# axiom_beta_plugin_module_3xPMOD_v1_1.net
KiCad netlist of a schematic drawn in EAGLE
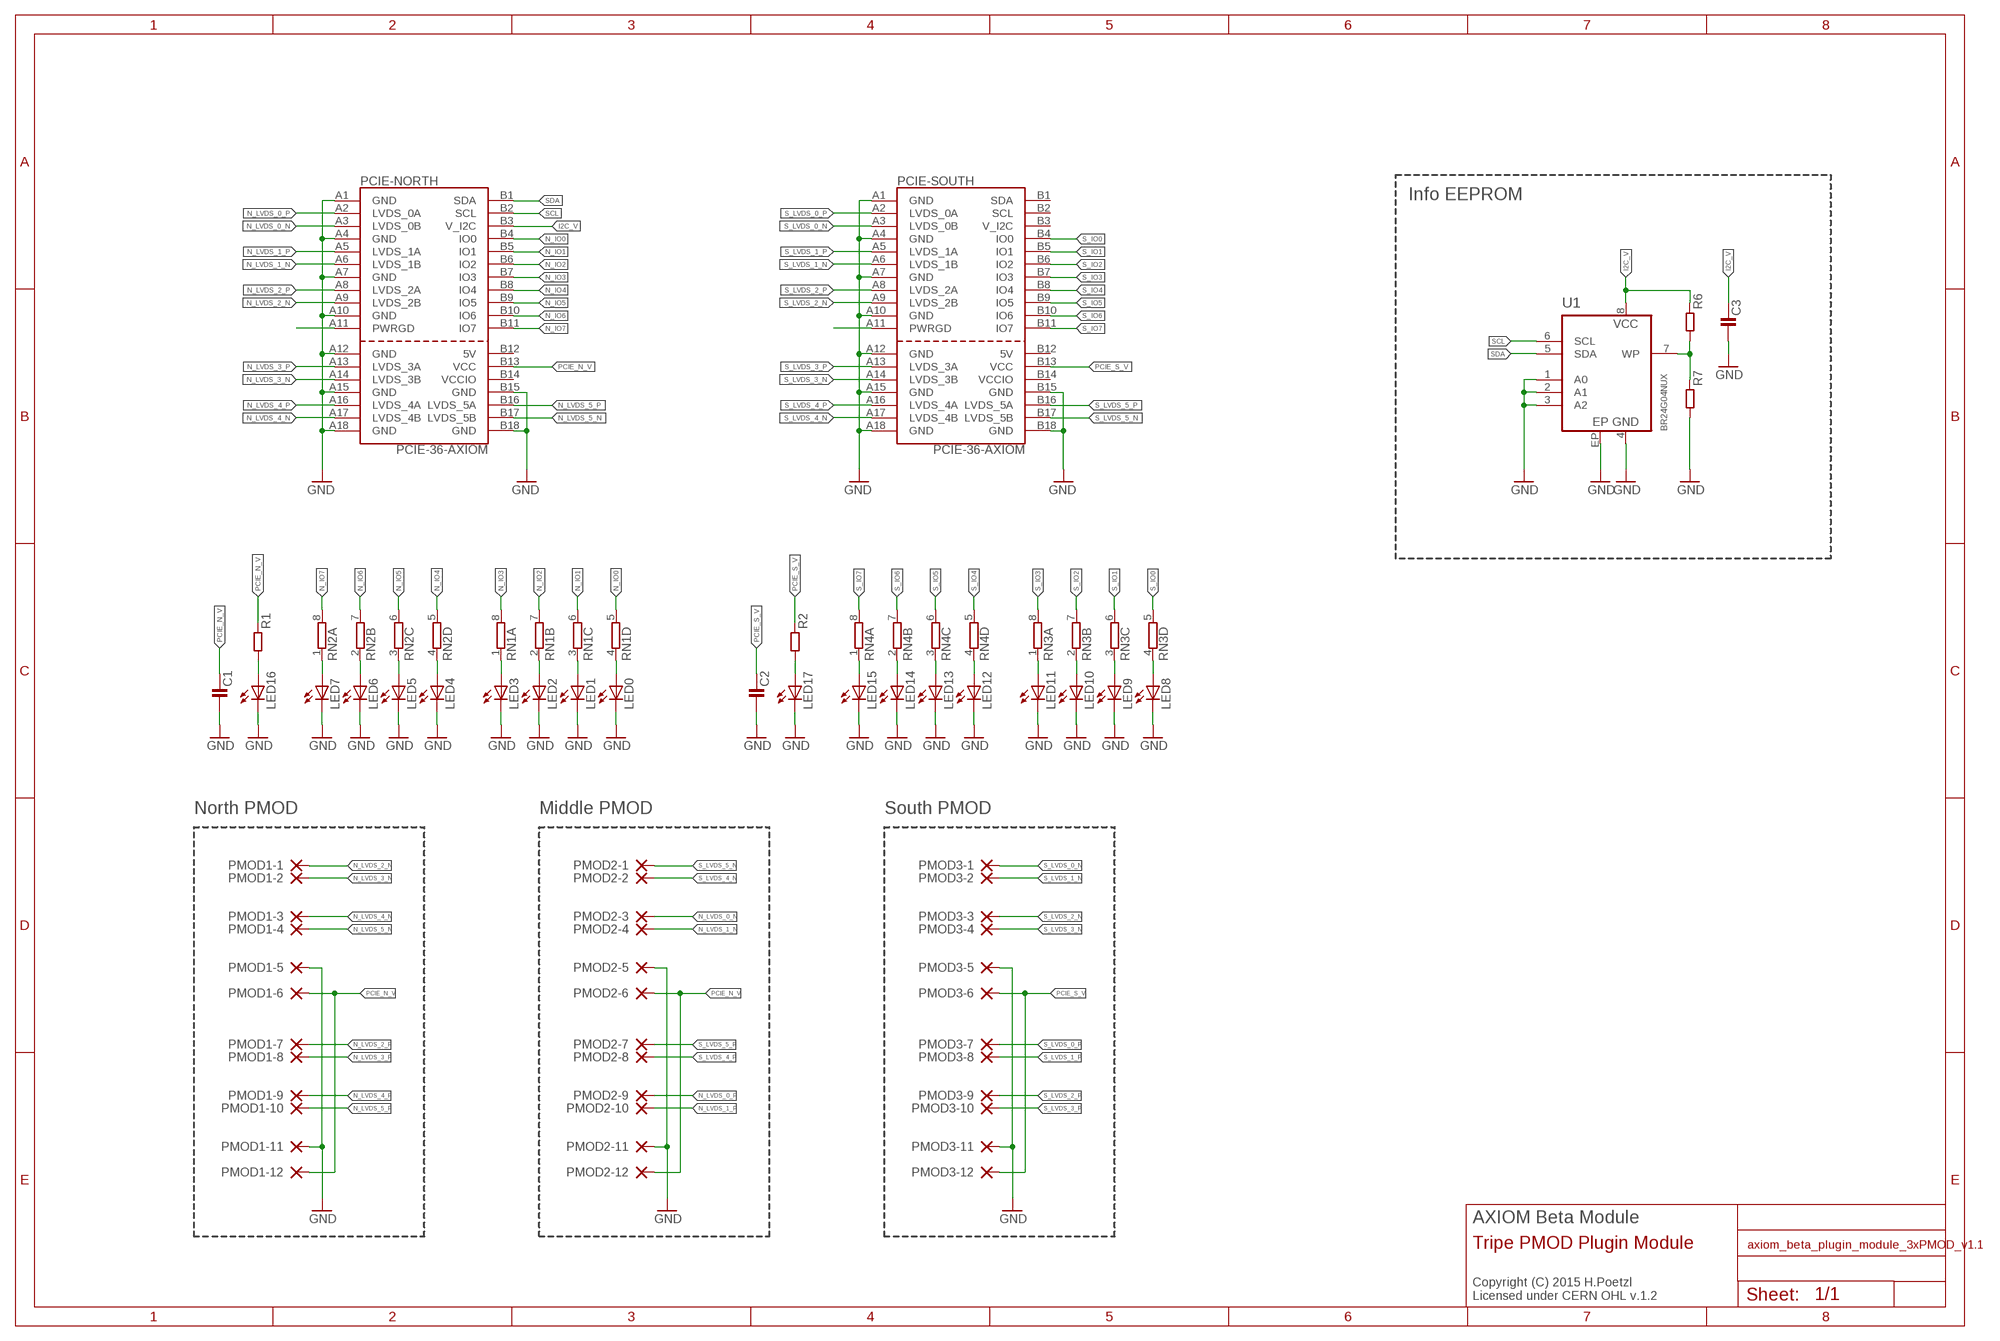
[diagram p0: schematic, sheet 1]

(export (version "E")
  (design (tool "Eeschema 10.0.6"))
  (components
    (comp (ref "C1")
      (value "C1206-A")
      (footprint "eagle-import:1206-A")
      (libsource (lib "eagle-import") (part "C1206-A"))
    )
    (comp (ref "C2")
      (value "C1206-A")
      (footprint "eagle-import:1206-A")
      (libsource (lib "eagle-import") (part "C1206-A"))
    )
    (comp (ref "C3")
      (value "C0402-B")
      (footprint "eagle-import:0402-B")
      (libsource (lib "eagle-import") (part "C0402-B"))
    )
    (comp (ref "LED0")
      (value "LEDCHIPLED_0603")
      (footprint "eagle-import:CHIPLED_0603")
      (libsource (lib "eagle-import") (part "LEDCHIPLED_0603"))
    )
    (comp (ref "LED1")
      (value "LEDCHIPLED_0603")
      (footprint "eagle-import:CHIPLED_0603")
      (libsource (lib "eagle-import") (part "LEDCHIPLED_0603"))
    )
    (comp (ref "LED2")
      (value "LEDCHIPLED_0603")
      (footprint "eagle-import:CHIPLED_0603")
      (libsource (lib "eagle-import") (part "LEDCHIPLED_0603"))
    )
    (comp (ref "LED3")
      (value "LEDCHIPLED_0603")
      (footprint "eagle-import:CHIPLED_0603")
      (libsource (lib "eagle-import") (part "LEDCHIPLED_0603"))
    )
    (comp (ref "LED4")
      (value "LEDCHIPLED_0603")
      (footprint "eagle-import:CHIPLED_0603")
      (libsource (lib "eagle-import") (part "LEDCHIPLED_0603"))
    )
    (comp (ref "LED5")
      (value "LEDCHIPLED_0603")
      (footprint "eagle-import:CHIPLED_0603")
      (libsource (lib "eagle-import") (part "LEDCHIPLED_0603"))
    )
    (comp (ref "LED6")
      (value "LEDCHIPLED_0603")
      (footprint "eagle-import:CHIPLED_0603")
      (libsource (lib "eagle-import") (part "LEDCHIPLED_0603"))
    )
    (comp (ref "LED7")
      (value "LEDCHIPLED_0603")
      (footprint "eagle-import:CHIPLED_0603")
      (libsource (lib "eagle-import") (part "LEDCHIPLED_0603"))
    )
    (comp (ref "LED8")
      (value "LEDCHIPLED_0603")
      (footprint "eagle-import:CHIPLED_0603")
      (libsource (lib "eagle-import") (part "LEDCHIPLED_0603"))
    )
    (comp (ref "LED9")
      (value "LEDCHIPLED_0603")
      (footprint "eagle-import:CHIPLED_0603")
      (libsource (lib "eagle-import") (part "LEDCHIPLED_0603"))
    )
    (comp (ref "LED10")
      (value "LEDCHIPLED_0603")
      (footprint "eagle-import:CHIPLED_0603")
      (libsource (lib "eagle-import") (part "LEDCHIPLED_0603"))
    )
    (comp (ref "LED11")
      (value "LEDCHIPLED_0603")
      (footprint "eagle-import:CHIPLED_0603")
      (libsource (lib "eagle-import") (part "LEDCHIPLED_0603"))
    )
    (comp (ref "LED12")
      (value "LEDCHIPLED_0603")
      (footprint "eagle-import:CHIPLED_0603")
      (libsource (lib "eagle-import") (part "LEDCHIPLED_0603"))
    )
    (comp (ref "LED13")
      (value "LEDCHIPLED_0603")
      (footprint "eagle-import:CHIPLED_0603")
      (libsource (lib "eagle-import") (part "LEDCHIPLED_0603"))
    )
    (comp (ref "LED14")
      (value "LEDCHIPLED_0603")
      (footprint "eagle-import:CHIPLED_0603")
      (libsource (lib "eagle-import") (part "LEDCHIPLED_0603"))
    )
    (comp (ref "LED15")
      (value "LEDCHIPLED_0603")
      (footprint "eagle-import:CHIPLED_0603")
      (libsource (lib "eagle-import") (part "LEDCHIPLED_0603"))
    )
    (comp (ref "LED16")
      (value "LEDCHIPLED_0603")
      (footprint "eagle-import:CHIPLED_0603")
      (libsource (lib "eagle-import") (part "LEDCHIPLED_0603"))
    )
    (comp (ref "LED17")
      (value "LEDCHIPLED_0603")
      (footprint "eagle-import:CHIPLED_0603")
      (libsource (lib "eagle-import") (part "LEDCHIPLED_0603"))
    )
    (comp (ref "PCIE-NORTH")
      (value "PCIE-36-AXIOM")
      (footprint "eagle-import:PCIE-36-AXIOM")
      (libsource (lib "eagle-import") (part "PCIE-36-AXIOM"))
    )
    (comp (ref "PCIE-SOUTH")
      (value "PCIE-36-AXIOM")
      (footprint "eagle-import:PCIE-36-AXIOM")
      (libsource (lib "eagle-import") (part "PCIE-36-AXIOM"))
    )
    (comp (ref "PMOD1-1")
      (value "SMD-PAD1.6X3.8MM-U")
      (footprint "eagle-import:1.6X3.8U-MM")
      (libsource (lib "eagle-import") (part "SMD-PAD1.6X3.8MM-U"))
    )
    (comp (ref "PMOD1-2")
      (value "SMD-PAD1.6X3.8MM-U")
      (footprint "eagle-import:1.6X3.8U-MM")
      (libsource (lib "eagle-import") (part "SMD-PAD1.6X3.8MM-U"))
    )
    (comp (ref "PMOD1-3")
      (value "SMD-PAD1.6X3.8MM-U")
      (footprint "eagle-import:1.6X3.8U-MM")
      (libsource (lib "eagle-import") (part "SMD-PAD1.6X3.8MM-U"))
    )
    (comp (ref "PMOD1-4")
      (value "SMD-PAD1.6X3.8MM-U")
      (footprint "eagle-import:1.6X3.8U-MM")
      (libsource (lib "eagle-import") (part "SMD-PAD1.6X3.8MM-U"))
    )
    (comp (ref "PMOD1-5")
      (value "SMD-PAD1.6X3.8MM-U")
      (footprint "eagle-import:1.6X3.8U-MM")
      (libsource (lib "eagle-import") (part "SMD-PAD1.6X3.8MM-U"))
    )
    (comp (ref "PMOD1-6")
      (value "SMD-PAD1.6X3.8MM-U")
      (footprint "eagle-import:1.6X3.8U-MM")
      (libsource (lib "eagle-import") (part "SMD-PAD1.6X3.8MM-U"))
    )
    (comp (ref "PMOD1-7")
      (value "SMD-PAD1.6X3.8MM-U")
      (footprint "eagle-import:1.6X3.8U-MM")
      (libsource (lib "eagle-import") (part "SMD-PAD1.6X3.8MM-U"))
    )
    (comp (ref "PMOD1-8")
      (value "SMD-PAD1.6X3.8MM-U")
      (footprint "eagle-import:1.6X3.8U-MM")
      (libsource (lib "eagle-import") (part "SMD-PAD1.6X3.8MM-U"))
    )
    (comp (ref "PMOD1-9")
      (value "SMD-PAD1.6X3.8MM-U")
      (footprint "eagle-import:1.6X3.8U-MM")
      (libsource (lib "eagle-import") (part "SMD-PAD1.6X3.8MM-U"))
    )
    (comp (ref "PMOD1-10")
      (value "SMD-PAD1.6X3.8MM-U")
      (footprint "eagle-import:1.6X3.8U-MM")
      (libsource (lib "eagle-import") (part "SMD-PAD1.6X3.8MM-U"))
    )
    (comp (ref "PMOD1-11")
      (value "SMD-PAD1.6X3.8MM-U")
      (footprint "eagle-import:1.6X3.8U-MM")
      (libsource (lib "eagle-import") (part "SMD-PAD1.6X3.8MM-U"))
    )
    (comp (ref "PMOD1-12")
      (value "SMD-PAD1.6X3.8MM-U")
      (footprint "eagle-import:1.6X3.8U-MM")
      (libsource (lib "eagle-import") (part "SMD-PAD1.6X3.8MM-U"))
    )
    (comp (ref "PMOD2-1")
      (value "SMD-PAD1.6X3.8MM-U")
      (footprint "eagle-import:1.6X3.8U-MM")
      (libsource (lib "eagle-import") (part "SMD-PAD1.6X3.8MM-U"))
    )
    (comp (ref "PMOD2-2")
      (value "SMD-PAD1.6X3.8MM-U")
      (footprint "eagle-import:1.6X3.8U-MM")
      (libsource (lib "eagle-import") (part "SMD-PAD1.6X3.8MM-U"))
    )
    (comp (ref "PMOD2-3")
      (value "SMD-PAD1.6X3.8MM-U")
      (footprint "eagle-import:1.6X3.8U-MM")
      (libsource (lib "eagle-import") (part "SMD-PAD1.6X3.8MM-U"))
    )
    (comp (ref "PMOD2-4")
      (value "SMD-PAD1.6X3.8MM-U")
      (footprint "eagle-import:1.6X3.8U-MM")
      (libsource (lib "eagle-import") (part "SMD-PAD1.6X3.8MM-U"))
    )
    (comp (ref "PMOD2-5")
      (value "SMD-PAD1.6X3.8MM-U")
      (footprint "eagle-import:1.6X3.8U-MM")
      (libsource (lib "eagle-import") (part "SMD-PAD1.6X3.8MM-U"))
    )
    (comp (ref "PMOD2-6")
      (value "SMD-PAD1.6X3.8MM-U")
      (footprint "eagle-import:1.6X3.8U-MM")
      (libsource (lib "eagle-import") (part "SMD-PAD1.6X3.8MM-U"))
    )
    (comp (ref "PMOD2-7")
      (value "SMD-PAD1.6X3.8MM-U")
      (footprint "eagle-import:1.6X3.8U-MM")
      (libsource (lib "eagle-import") (part "SMD-PAD1.6X3.8MM-U"))
    )
    (comp (ref "PMOD2-8")
      (value "SMD-PAD1.6X3.8MM-U")
      (footprint "eagle-import:1.6X3.8U-MM")
      (libsource (lib "eagle-import") (part "SMD-PAD1.6X3.8MM-U"))
    )
    (comp (ref "PMOD2-9")
      (value "SMD-PAD1.6X3.8MM-U")
      (footprint "eagle-import:1.6X3.8U-MM")
      (libsource (lib "eagle-import") (part "SMD-PAD1.6X3.8MM-U"))
    )
    (comp (ref "PMOD2-10")
      (value "SMD-PAD1.6X3.8MM-U")
      (footprint "eagle-import:1.6X3.8U-MM")
      (libsource (lib "eagle-import") (part "SMD-PAD1.6X3.8MM-U"))
    )
    (comp (ref "PMOD2-11")
      (value "SMD-PAD1.6X3.8MM-U")
      (footprint "eagle-import:1.6X3.8U-MM")
      (libsource (lib "eagle-import") (part "SMD-PAD1.6X3.8MM-U"))
    )
    (comp (ref "PMOD2-12")
      (value "SMD-PAD1.6X3.8MM-U")
      (footprint "eagle-import:1.6X3.8U-MM")
      (libsource (lib "eagle-import") (part "SMD-PAD1.6X3.8MM-U"))
    )
    (comp (ref "PMOD3-1")
      (value "SMD-PAD1.6X3.8MM-U")
      (footprint "eagle-import:1.6X3.8U-MM")
      (libsource (lib "eagle-import") (part "SMD-PAD1.6X3.8MM-U"))
    )
    (comp (ref "PMOD3-2")
      (value "SMD-PAD1.6X3.8MM-U")
      (footprint "eagle-import:1.6X3.8U-MM")
      (libsource (lib "eagle-import") (part "SMD-PAD1.6X3.8MM-U"))
    )
    (comp (ref "PMOD3-3")
      (value "SMD-PAD1.6X3.8MM-U")
      (footprint "eagle-import:1.6X3.8U-MM")
      (libsource (lib "eagle-import") (part "SMD-PAD1.6X3.8MM-U"))
    )
    (comp (ref "PMOD3-4")
      (value "SMD-PAD1.6X3.8MM-U")
      (footprint "eagle-import:1.6X3.8U-MM")
      (libsource (lib "eagle-import") (part "SMD-PAD1.6X3.8MM-U"))
    )
    (comp (ref "PMOD3-5")
      (value "SMD-PAD1.6X3.8MM-U")
      (footprint "eagle-import:1.6X3.8U-MM")
      (libsource (lib "eagle-import") (part "SMD-PAD1.6X3.8MM-U"))
    )
    (comp (ref "PMOD3-6")
      (value "SMD-PAD1.6X3.8MM-U")
      (footprint "eagle-import:1.6X3.8U-MM")
      (libsource (lib "eagle-import") (part "SMD-PAD1.6X3.8MM-U"))
    )
    (comp (ref "PMOD3-7")
      (value "SMD-PAD1.6X3.8MM-U")
      (footprint "eagle-import:1.6X3.8U-MM")
      (libsource (lib "eagle-import") (part "SMD-PAD1.6X3.8MM-U"))
    )
    (comp (ref "PMOD3-8")
      (value "SMD-PAD1.6X3.8MM-U")
      (footprint "eagle-import:1.6X3.8U-MM")
      (libsource (lib "eagle-import") (part "SMD-PAD1.6X3.8MM-U"))
    )
    (comp (ref "PMOD3-9")
      (value "SMD-PAD1.6X3.8MM-U")
      (footprint "eagle-import:1.6X3.8U-MM")
      (libsource (lib "eagle-import") (part "SMD-PAD1.6X3.8MM-U"))
    )
    (comp (ref "PMOD3-10")
      (value "SMD-PAD1.6X3.8MM-U")
      (footprint "eagle-import:1.6X3.8U-MM")
      (libsource (lib "eagle-import") (part "SMD-PAD1.6X3.8MM-U"))
    )
    (comp (ref "PMOD3-11")
      (value "SMD-PAD1.6X3.8MM-U")
      (footprint "eagle-import:1.6X3.8U-MM")
      (libsource (lib "eagle-import") (part "SMD-PAD1.6X3.8MM-U"))
    )
    (comp (ref "PMOD3-12")
      (value "SMD-PAD1.6X3.8MM-U")
      (footprint "eagle-import:1.6X3.8U-MM")
      (libsource (lib "eagle-import") (part "SMD-PAD1.6X3.8MM-U"))
    )
    (comp (ref "R1")
      (value "R0402-B")
      (footprint "eagle-import:0402-B")
      (libsource (lib "eagle-import") (part "R0402-B"))
    )
    (comp (ref "R2")
      (value "R0402-B")
      (footprint "eagle-import:0402-B")
      (libsource (lib "eagle-import") (part "R0402-B"))
    )
    (comp (ref "R6")
      (value "R0402-B")
      (footprint "eagle-import:0402-B")
      (libsource (lib "eagle-import") (part "R0402-B"))
    )
    (comp (ref "R7")
      (value "R0402-B")
      (footprint "eagle-import:0402-B")
      (libsource (lib "eagle-import") (part "R0402-B"))
    )
    (comp (ref "RN1")
      (value "4R-NCAY16")
      (footprint "eagle-import:CAY16")
      (libsource (lib "eagle-import") (part "4R-NCAY16"))
    )
    (comp (ref "RN2")
      (value "4R-NCAY16")
      (footprint "eagle-import:CAY16")
      (libsource (lib "eagle-import") (part "4R-NCAY16"))
    )
    (comp (ref "RN3")
      (value "4R-NCAY16")
      (footprint "eagle-import:CAY16")
      (libsource (lib "eagle-import") (part "4R-NCAY16"))
    )
    (comp (ref "RN4")
      (value "4R-NCAY16")
      (footprint "eagle-import:CAY16")
      (libsource (lib "eagle-import") (part "4R-NCAY16"))
    )
    (comp (ref "U1")
      (value "BR24G04NUX")
      (footprint "eagle-import:DFN200X300X100-9N")
      (libsource (lib "eagle-import") (part "BR24G04NUX"))
    )
  )
  (nets
    (net (code "1") (name "GND") (class "Default")
      (node (ref "C1") (pin "2") (pinfunction "2_2") (pintype "passive"))
      (node (ref "C2") (pin "2") (pinfunction "2_2") (pintype "passive"))
      (node (ref "C3") (pin "2") (pinfunction "2_2") (pintype "passive"))
      (node (ref "LED0") (pin "C") (pinfunction "C_C") (pintype "passive"))
      (node (ref "LED1") (pin "C") (pinfunction "C_C") (pintype "passive"))
      (node (ref "LED10") (pin "C") (pinfunction "C_C") (pintype "passive"))
      (node (ref "LED11") (pin "C") (pinfunction "C_C") (pintype "passive"))
      (node (ref "LED12") (pin "C") (pinfunction "C_C") (pintype "passive"))
      (node (ref "LED13") (pin "C") (pinfunction "C_C") (pintype "passive"))
      (node (ref "LED14") (pin "C") (pinfunction "C_C") (pintype "passive"))
      (node (ref "LED15") (pin "C") (pinfunction "C_C") (pintype "passive"))
      (node (ref "LED16") (pin "C") (pinfunction "C_C") (pintype "passive"))
      (node (ref "LED17") (pin "C") (pinfunction "C_C") (pintype "passive"))
      (node (ref "LED2") (pin "C") (pinfunction "C_C") (pintype "passive"))
      (node (ref "LED3") (pin "C") (pinfunction "C_C") (pintype "passive"))
      (node (ref "LED4") (pin "C") (pinfunction "C_C") (pintype "passive"))
      (node (ref "LED5") (pin "C") (pinfunction "C_C") (pintype "passive"))
      (node (ref "LED6") (pin "C") (pinfunction "C_C") (pintype "passive"))
      (node (ref "LED7") (pin "C") (pinfunction "C_C") (pintype "passive"))
      (node (ref "LED8") (pin "C") (pinfunction "C_C") (pintype "passive"))
      (node (ref "LED9") (pin "C") (pinfunction "C_C") (pintype "passive"))
      (node (ref "PCIE-NORTH") (pin "A1") (pinfunction "GND_A1") (pintype "passive"))
      (node (ref "PCIE-NORTH") (pin "A10") (pinfunction "GND_A10") (pintype "passive"))
      (node (ref "PCIE-NORTH") (pin "A12") (pinfunction "GND_A12") (pintype "passive"))
      (node (ref "PCIE-NORTH") (pin "A15") (pinfunction "GND_A15") (pintype "passive"))
      (node (ref "PCIE-NORTH") (pin "A18") (pinfunction "GND_A18") (pintype "passive"))
      (node (ref "PCIE-NORTH") (pin "A4") (pinfunction "GND_A4") (pintype "passive"))
      (node (ref "PCIE-NORTH") (pin "A7") (pinfunction "GND_A7") (pintype "passive"))
      (node (ref "PCIE-NORTH") (pin "B15") (pinfunction "GND_B15") (pintype "passive"))
      (node (ref "PCIE-NORTH") (pin "B18") (pinfunction "GND_B18") (pintype "passive"))
      (node (ref "PCIE-SOUTH") (pin "A1") (pinfunction "GND_A1") (pintype "passive"))
      (node (ref "PCIE-SOUTH") (pin "A10") (pinfunction "GND_A10") (pintype "passive"))
      (node (ref "PCIE-SOUTH") (pin "A12") (pinfunction "GND_A12") (pintype "passive"))
      (node (ref "PCIE-SOUTH") (pin "A15") (pinfunction "GND_A15") (pintype "passive"))
      (node (ref "PCIE-SOUTH") (pin "A18") (pinfunction "GND_A18") (pintype "passive"))
      (node (ref "PCIE-SOUTH") (pin "A4") (pinfunction "GND_A4") (pintype "passive"))
      (node (ref "PCIE-SOUTH") (pin "A7") (pinfunction "GND_A7") (pintype "passive"))
      (node (ref "PCIE-SOUTH") (pin "B15") (pinfunction "GND_B15") (pintype "passive"))
      (node (ref "PCIE-SOUTH") (pin "B18") (pinfunction "GND_B18") (pintype "passive"))
      (node (ref "PMOD1-11") (pin "1") (pinfunction "P_1") (pintype "passive"))
      (node (ref "PMOD1-5") (pin "1") (pinfunction "P_1") (pintype "passive"))
      (node (ref "PMOD2-11") (pin "1") (pinfunction "P_1") (pintype "passive"))
      (node (ref "PMOD2-5") (pin "1") (pinfunction "P_1") (pintype "passive"))
      (node (ref "PMOD3-11") (pin "1") (pinfunction "P_1") (pintype "passive"))
      (node (ref "PMOD3-5") (pin "1") (pinfunction "P_1") (pintype "passive"))
      (node (ref "R7") (pin "2") (pinfunction "2_2") (pintype "passive"))
      (node (ref "U1") (pin "1") (pinfunction "A0_1") (pintype "input"))
      (node (ref "U1") (pin "2") (pinfunction "A1_2") (pintype "input"))
      (node (ref "U1") (pin "3") (pinfunction "A2_3") (pintype "input"))
      (node (ref "U1") (pin "4") (pinfunction "GND_4") (pintype "passive"))
      (node (ref "U1") (pin "EP") (pinfunction "EP_EP") (pintype "passive"))
    )
    (net (code "2") (name "I2C_V") (class "Default")
      (node (ref "C3") (pin "1") (pinfunction "1_1") (pintype "passive"))
      (node (ref "PCIE-NORTH") (pin "B3") (pinfunction "V_I2C_B3") (pintype "passive"))
      (node (ref "R6") (pin "1") (pinfunction "1_1") (pintype "passive"))
      (node (ref "U1") (pin "8") (pinfunction "VCC_8") (pintype "power_in"))
    )
    (net (code "3") (name "N_IO0") (class "Default")
      (node (ref "PCIE-NORTH") (pin "B4") (pinfunction "IO0_B4") (pintype "passive"))
      (node (ref "RN1") (pin "5") (pinfunction "2_5") (pintype "passive"))
    )
    (net (code "4") (name "N_IO1") (class "Default")
      (node (ref "PCIE-NORTH") (pin "B5") (pinfunction "IO1_B5") (pintype "passive"))
      (node (ref "RN1") (pin "6") (pinfunction "2_6") (pintype "passive"))
    )
    (net (code "5") (name "N_IO2") (class "Default")
      (node (ref "PCIE-NORTH") (pin "B6") (pinfunction "IO2_B6") (pintype "passive"))
      (node (ref "RN1") (pin "7") (pinfunction "2_7") (pintype "passive"))
    )
    (net (code "6") (name "N_IO3") (class "Default")
      (node (ref "PCIE-NORTH") (pin "B7") (pinfunction "IO3_B7") (pintype "passive"))
      (node (ref "RN1") (pin "8") (pinfunction "2_8") (pintype "passive"))
    )
    (net (code "7") (name "N_IO4") (class "Default")
      (node (ref "PCIE-NORTH") (pin "B8") (pinfunction "IO4_B8") (pintype "passive"))
      (node (ref "RN2") (pin "5") (pinfunction "2_5") (pintype "passive"))
    )
    (net (code "8") (name "N_IO5") (class "Default")
      (node (ref "PCIE-NORTH") (pin "B9") (pinfunction "IO5_B9") (pintype "passive"))
      (node (ref "RN2") (pin "6") (pinfunction "2_6") (pintype "passive"))
    )
    (net (code "9") (name "N_IO6") (class "Default")
      (node (ref "PCIE-NORTH") (pin "B10") (pinfunction "IO6_B10") (pintype "passive"))
      (node (ref "RN2") (pin "7") (pinfunction "2_7") (pintype "passive"))
    )
    (net (code "10") (name "N_IO7") (class "Default")
      (node (ref "PCIE-NORTH") (pin "B11") (pinfunction "IO7_B11") (pintype "passive"))
      (node (ref "RN2") (pin "8") (pinfunction "2_8") (pintype "passive"))
    )
    (net (code "11") (name "N_LVDS_0_N") (class "Default")
      (node (ref "PCIE-NORTH") (pin "A3") (pinfunction "LVDS_0B_A3") (pintype "passive"))
      (node (ref "PMOD2-3") (pin "1") (pinfunction "P_1") (pintype "passive"))
    )
    (net (code "12") (name "N_LVDS_0_P") (class "Default")
      (node (ref "PCIE-NORTH") (pin "A2") (pinfunction "LVDS_0A_A2") (pintype "passive"))
      (node (ref "PMOD2-9") (pin "1") (pinfunction "P_1") (pintype "passive"))
    )
    (net (code "13") (name "N_LVDS_1_N") (class "Default")
      (node (ref "PCIE-NORTH") (pin "A6") (pinfunction "LVDS_1B_A6") (pintype "passive"))
      (node (ref "PMOD2-4") (pin "1") (pinfunction "P_1") (pintype "passive"))
    )
    (net (code "14") (name "N_LVDS_1_P") (class "Default")
      (node (ref "PCIE-NORTH") (pin "A5") (pinfunction "LVDS_1A_A5") (pintype "passive"))
      (node (ref "PMOD2-10") (pin "1") (pinfunction "P_1") (pintype "passive"))
    )
    (net (code "15") (name "N_LVDS_2_N") (class "Default")
      (node (ref "PCIE-NORTH") (pin "A9") (pinfunction "LVDS_2B_A9") (pintype "passive"))
      (node (ref "PMOD1-1") (pin "1") (pinfunction "P_1") (pintype "passive"))
    )
    (net (code "16") (name "N_LVDS_2_P") (class "Default")
      (node (ref "PCIE-NORTH") (pin "A8") (pinfunction "LVDS_2A_A8") (pintype "passive"))
      (node (ref "PMOD1-7") (pin "1") (pinfunction "P_1") (pintype "passive"))
    )
    (net (code "17") (name "N_LVDS_3_N") (class "Default")
      (node (ref "PCIE-NORTH") (pin "A14") (pinfunction "LVDS_3B_A14") (pintype "passive"))
      (node (ref "PMOD1-2") (pin "1") (pinfunction "P_1") (pintype "passive"))
    )
    (net (code "18") (name "N_LVDS_3_P") (class "Default")
      (node (ref "PCIE-NORTH") (pin "A13") (pinfunction "LVDS_3A_A13") (pintype "passive"))
      (node (ref "PMOD1-8") (pin "1") (pinfunction "P_1") (pintype "passive"))
    )
    (net (code "19") (name "N_LVDS_4_N") (class "Default")
      (node (ref "PCIE-NORTH") (pin "A17") (pinfunction "LVDS_4B_A17") (pintype "passive"))
      (node (ref "PMOD1-3") (pin "1") (pinfunction "P_1") (pintype "passive"))
    )
    (net (code "20") (name "N_LVDS_4_P") (class "Default")
      (node (ref "PCIE-NORTH") (pin "A16") (pinfunction "LVDS_4A_A16") (pintype "passive"))
      (node (ref "PMOD1-9") (pin "1") (pinfunction "P_1") (pintype "passive"))
    )
    (net (code "21") (name "N_LVDS_5_N") (class "Default")
      (node (ref "PCIE-NORTH") (pin "B17") (pinfunction "LVDS_5B_B17") (pintype "passive"))
      (node (ref "PMOD1-4") (pin "1") (pinfunction "P_1") (pintype "passive"))
    )
    (net (code "22") (name "N_LVDS_5_P") (class "Default")
      (node (ref "PCIE-NORTH") (pin "B16") (pinfunction "LVDS_5A_B16") (pintype "passive"))
      (node (ref "PMOD1-10") (pin "1") (pinfunction "P_1") (pintype "passive"))
    )
    (net (code "23") (name "Net-(LED3-PadA)") (class "Default")
      (node (ref "LED3") (pin "A") (pinfunction "A_A") (pintype "passive"))
      (node (ref "RN1") (pin "1") (pinfunction "1_1") (pintype "passive"))
    )
    (net (code "24") (name "Net-(LED7-PadA)") (class "Default")
      (node (ref "LED7") (pin "A") (pinfunction "A_A") (pintype "passive"))
      (node (ref "RN2") (pin "1") (pinfunction "1_1") (pintype "passive"))
    )
    (net (code "25") (name "Net-(LED11-PadA)") (class "Default")
      (node (ref "LED11") (pin "A") (pinfunction "A_A") (pintype "passive"))
      (node (ref "RN3") (pin "1") (pinfunction "1_1") (pintype "passive"))
    )
    (net (code "26") (name "Net-(LED15-PadA)") (class "Default")
      (node (ref "LED15") (pin "A") (pinfunction "A_A") (pintype "passive"))
      (node (ref "RN4") (pin "1") (pinfunction "1_1") (pintype "passive"))
    )
    (net (code "27") (name "Net-(LED16-PadA)") (class "Default")
      (node (ref "LED16") (pin "A") (pinfunction "A_A") (pintype "passive"))
      (node (ref "R1") (pin "2") (pinfunction "2_2") (pintype "passive"))
    )
    (net (code "28") (name "Net-(LED17-PadA)") (class "Default")
      (node (ref "LED17") (pin "A") (pinfunction "A_A") (pintype "passive"))
      (node (ref "R2") (pin "2") (pinfunction "2_2") (pintype "passive"))
    )
    (net (code "29") (name "Net-(RN1B-1)") (class "Default")
      (node (ref "LED2") (pin "A") (pinfunction "A_A") (pintype "passive"))
      (node (ref "RN1") (pin "2") (pinfunction "1_2") (pintype "passive"))
    )
    (net (code "30") (name "Net-(RN1C-1)") (class "Default")
      (node (ref "LED1") (pin "A") (pinfunction "A_A") (pintype "passive"))
      (node (ref "RN1") (pin "3") (pinfunction "1_3") (pintype "passive"))
    )
    (net (code "31") (name "Net-(RN1D-1)") (class "Default")
      (node (ref "LED0") (pin "A") (pinfunction "A_A") (pintype "passive"))
      (node (ref "RN1") (pin "4") (pinfunction "1_4") (pintype "passive"))
    )
    (net (code "32") (name "Net-(RN2B-1)") (class "Default")
      (node (ref "LED6") (pin "A") (pinfunction "A_A") (pintype "passive"))
      (node (ref "RN2") (pin "2") (pinfunction "1_2") (pintype "passive"))
    )
    (net (code "33") (name "Net-(RN2C-1)") (class "Default")
      (node (ref "LED5") (pin "A") (pinfunction "A_A") (pintype "passive"))
      (node (ref "RN2") (pin "3") (pinfunction "1_3") (pintype "passive"))
    )
    (net (code "34") (name "Net-(RN2D-1)") (class "Default")
      (node (ref "LED4") (pin "A") (pinfunction "A_A") (pintype "passive"))
      (node (ref "RN2") (pin "4") (pinfunction "1_4") (pintype "passive"))
    )
    (net (code "35") (name "Net-(RN3B-1)") (class "Default")
      (node (ref "LED10") (pin "A") (pinfunction "A_A") (pintype "passive"))
      (node (ref "RN3") (pin "2") (pinfunction "1_2") (pintype "passive"))
    )
    (net (code "36") (name "Net-(RN3C-1)") (class "Default")
      (node (ref "LED9") (pin "A") (pinfunction "A_A") (pintype "passive"))
      (node (ref "RN3") (pin "3") (pinfunction "1_3") (pintype "passive"))
    )
    (net (code "37") (name "Net-(RN3D-1)") (class "Default")
      (node (ref "LED8") (pin "A") (pinfunction "A_A") (pintype "passive"))
      (node (ref "RN3") (pin "4") (pinfunction "1_4") (pintype "passive"))
    )
    (net (code "38") (name "Net-(RN4B-1)") (class "Default")
      (node (ref "LED14") (pin "A") (pinfunction "A_A") (pintype "passive"))
      (node (ref "RN4") (pin "2") (pinfunction "1_2") (pintype "passive"))
    )
    (net (code "39") (name "Net-(RN4C-1)") (class "Default")
      (node (ref "LED13") (pin "A") (pinfunction "A_A") (pintype "passive"))
      (node (ref "RN4") (pin "3") (pinfunction "1_3") (pintype "passive"))
    )
    (net (code "40") (name "Net-(RN4D-1)") (class "Default")
      (node (ref "LED12") (pin "A") (pinfunction "A_A") (pintype "passive"))
      (node (ref "RN4") (pin "4") (pinfunction "1_4") (pintype "passive"))
    )
    (net (code "41") (name "Net-(U1-WP)") (class "Default")
      (node (ref "R6") (pin "2") (pinfunction "2_2") (pintype "passive"))
      (node (ref "R7") (pin "1") (pinfunction "1_1") (pintype "passive"))
      (node (ref "U1") (pin "7") (pinfunction "WP_7") (pintype "input"))
    )
    (net (code "42") (name "PCIE_N_V") (class "Default")
      (node (ref "C1") (pin "1") (pinfunction "1_1") (pintype "passive"))
      (node (ref "PCIE-NORTH") (pin "B13") (pinfunction "VCC_B13") (pintype "passive"))
      (node (ref "PMOD1-12") (pin "1") (pinfunction "P_1") (pintype "passive"))
      (node (ref "PMOD1-6") (pin "1") (pinfunction "P_1") (pintype "passive"))
      (node (ref "PMOD2-12") (pin "1") (pinfunction "P_1") (pintype "passive"))
      (node (ref "PMOD2-6") (pin "1") (pinfunction "P_1") (pintype "passive"))
      (node (ref "R1") (pin "1") (pinfunction "1_1") (pintype "passive"))
    )
    (net (code "43") (name "PCIE_S_V") (class "Default")
      (node (ref "C2") (pin "1") (pinfunction "1_1") (pintype "passive"))
      (node (ref "PCIE-SOUTH") (pin "B13") (pinfunction "VCC_B13") (pintype "passive"))
      (node (ref "PMOD3-12") (pin "1") (pinfunction "P_1") (pintype "passive"))
      (node (ref "PMOD3-6") (pin "1") (pinfunction "P_1") (pintype "passive"))
      (node (ref "R2") (pin "1") (pinfunction "1_1") (pintype "passive"))
    )
    (net (code "44") (name "SCL") (class "Default")
      (node (ref "PCIE-NORTH") (pin "B2") (pinfunction "SCL_B2") (pintype "passive"))
      (node (ref "U1") (pin "6") (pinfunction "SCL_6") (pintype "input"))
    )
    (net (code "45") (name "SDA") (class "Default")
      (node (ref "PCIE-NORTH") (pin "B1") (pinfunction "SDA_B1") (pintype "passive"))
      (node (ref "U1") (pin "5") (pinfunction "SDA_5") (pintype "bidirectional"))
    )
    (net (code "46") (name "S_IO0") (class "Default")
      (node (ref "PCIE-SOUTH") (pin "B4") (pinfunction "IO0_B4") (pintype "passive"))
      (node (ref "RN3") (pin "5") (pinfunction "2_5") (pintype "passive"))
    )
    (net (code "47") (name "S_IO1") (class "Default")
      (node (ref "PCIE-SOUTH") (pin "B5") (pinfunction "IO1_B5") (pintype "passive"))
      (node (ref "RN3") (pin "6") (pinfunction "2_6") (pintype "passive"))
    )
    (net (code "48") (name "S_IO2") (class "Default")
      (node (ref "PCIE-SOUTH") (pin "B6") (pinfunction "IO2_B6") (pintype "passive"))
      (node (ref "RN3") (pin "7") (pinfunction "2_7") (pintype "passive"))
    )
    (net (code "49") (name "S_IO3") (class "Default")
      (node (ref "PCIE-SOUTH") (pin "B7") (pinfunction "IO3_B7") (pintype "passive"))
      (node (ref "RN3") (pin "8") (pinfunction "2_8") (pintype "passive"))
    )
    (net (code "50") (name "S_IO4") (class "Default")
      (node (ref "PCIE-SOUTH") (pin "B8") (pinfunction "IO4_B8") (pintype "passive"))
      (node (ref "RN4") (pin "5") (pinfunction "2_5") (pintype "passive"))
    )
    (net (code "51") (name "S_IO5") (class "Default")
      (node (ref "PCIE-SOUTH") (pin "B9") (pinfunction "IO5_B9") (pintype "passive"))
      (node (ref "RN4") (pin "6") (pinfunction "2_6") (pintype "passive"))
    )
    (net (code "52") (name "S_IO6") (class "Default")
      (node (ref "PCIE-SOUTH") (pin "B10") (pinfunction "IO6_B10") (pintype "passive"))
      (node (ref "RN4") (pin "7") (pinfunction "2_7") (pintype "passive"))
    )
    (net (code "53") (name "S_IO7") (class "Default")
      (node (ref "PCIE-SOUTH") (pin "B11") (pinfunction "IO7_B11") (pintype "passive"))
      (node (ref "RN4") (pin "8") (pinfunction "2_8") (pintype "passive"))
    )
    (net (code "54") (name "S_LVDS_0_N") (class "Default")
      (node (ref "PCIE-SOUTH") (pin "A3") (pinfunction "LVDS_0B_A3") (pintype "passive"))
      (node (ref "PMOD3-1") (pin "1") (pinfunction "P_1") (pintype "passive"))
    )
    (net (code "55") (name "S_LVDS_0_P") (class "Default")
      (node (ref "PCIE-SOUTH") (pin "A2") (pinfunction "LVDS_0A_A2") (pintype "passive"))
      (node (ref "PMOD3-7") (pin "1") (pinfunction "P_1") (pintype "passive"))
    )
    (net (code "56") (name "S_LVDS_1_N") (class "Default")
      (node (ref "PCIE-SOUTH") (pin "A6") (pinfunction "LVDS_1B_A6") (pintype "passive"))
      (node (ref "PMOD3-2") (pin "1") (pinfunction "P_1") (pintype "passive"))
    )
    (net (code "57") (name "S_LVDS_1_P") (class "Default")
      (node (ref "PCIE-SOUTH") (pin "A5") (pinfunction "LVDS_1A_A5") (pintype "passive"))
      (node (ref "PMOD3-8") (pin "1") (pinfunction "P_1") (pintype "passive"))
    )
    (net (code "58") (name "S_LVDS_2_N") (class "Default")
      (node (ref "PCIE-SOUTH") (pin "A9") (pinfunction "LVDS_2B_A9") (pintype "passive"))
      (node (ref "PMOD3-3") (pin "1") (pinfunction "P_1") (pintype "passive"))
    )
    (net (code "59") (name "S_LVDS_2_P") (class "Default")
      (node (ref "PCIE-SOUTH") (pin "A8") (pinfunction "LVDS_2A_A8") (pintype "passive"))
      (node (ref "PMOD3-9") (pin "1") (pinfunction "P_1") (pintype "passive"))
    )
    (net (code "60") (name "S_LVDS_3_N") (class "Default")
      (node (ref "PCIE-SOUTH") (pin "A14") (pinfunction "LVDS_3B_A14") (pintype "passive"))
      (node (ref "PMOD3-4") (pin "1") (pinfunction "P_1") (pintype "passive"))
    )
    (net (code "61") (name "S_LVDS_3_P") (class "Default")
      (node (ref "PCIE-SOUTH") (pin "A13") (pinfunction "LVDS_3A_A13") (pintype "passive"))
      (node (ref "PMOD3-10") (pin "1") (pinfunction "P_1") (pintype "passive"))
    )
    (net (code "62") (name "S_LVDS_4_N") (class "Default")
      (node (ref "PCIE-SOUTH") (pin "A17") (pinfunction "LVDS_4B_A17") (pintype "passive"))
      (node (ref "PMOD2-2") (pin "1") (pinfunction "P_1") (pintype "passive"))
    )
    (net (code "63") (name "S_LVDS_4_P") (class "Default")
      (node (ref "PCIE-SOUTH") (pin "A16") (pinfunction "LVDS_4A_A16") (pintype "passive"))
      (node (ref "PMOD2-8") (pin "1") (pinfunction "P_1") (pintype "passive"))
    )
    (net (code "64") (name "S_LVDS_5_N") (class "Default")
      (node (ref "PCIE-SOUTH") (pin "B17") (pinfunction "LVDS_5B_B17") (pintype "passive"))
      (node (ref "PMOD2-1") (pin "1") (pinfunction "P_1") (pintype "passive"))
    )
    (net (code "65") (name "S_LVDS_5_P") (class "Default")
      (node (ref "PCIE-SOUTH") (pin "B16") (pinfunction "LVDS_5A_B16") (pintype "passive"))
      (node (ref "PMOD2-7") (pin "1") (pinfunction "P_1") (pintype "passive"))
    )
    (net (code "66") (name "unconnected-(PCIE-NORTH-5V-PadB12)") (class "Default")
      (node (ref "PCIE-NORTH") (pin "B12") (pinfunction "5V_B12") (pintype "passive"))
    )
    (net (code "67") (name "unconnected-(PCIE-NORTH-PWRGD-PadA11)") (class "Default")
      (node (ref "PCIE-NORTH") (pin "A11") (pinfunction "PWRGD_A11") (pintype "passive"))
    )
    (net (code "68") (name "unconnected-(PCIE-NORTH-VCCIO-PadB14)") (class "Default")
      (node (ref "PCIE-NORTH") (pin "B14") (pinfunction "VCCIO_B14") (pintype "passive"))
    )
    (net (code "69") (name "unconnected-(PCIE-SOUTH-5V-PadB12)") (class "Default")
      (node (ref "PCIE-SOUTH") (pin "B12") (pinfunction "5V_B12") (pintype "passive"))
    )
    (net (code "70") (name "unconnected-(PCIE-SOUTH-PWRGD-PadA11)") (class "Default")
      (node (ref "PCIE-SOUTH") (pin "A11") (pinfunction "PWRGD_A11") (pintype "passive"))
    )
    (net (code "71") (name "unconnected-(PCIE-SOUTH-SCL-PadB2)") (class "Default")
      (node (ref "PCIE-SOUTH") (pin "B2") (pinfunction "SCL_B2") (pintype "passive"))
    )
    (net (code "72") (name "unconnected-(PCIE-SOUTH-SDA-PadB1)") (class "Default")
      (node (ref "PCIE-SOUTH") (pin "B1") (pinfunction "SDA_B1") (pintype "passive"))
    )
    (net (code "73") (name "unconnected-(PCIE-SOUTH-VCCIO-PadB14)") (class "Default")
      (node (ref "PCIE-SOUTH") (pin "B14") (pinfunction "VCCIO_B14") (pintype "passive"))
    )
    (net (code "74") (name "unconnected-(PCIE-SOUTH-V_I2C-PadB3)") (class "Default")
      (node (ref "PCIE-SOUTH") (pin "B3") (pinfunction "V_I2C_B3") (pintype "passive"))
    )
  )
)
